# SCH_MI_L_2024-02-24.net
KiCad netlist of a schematic drawn in EasyEDA
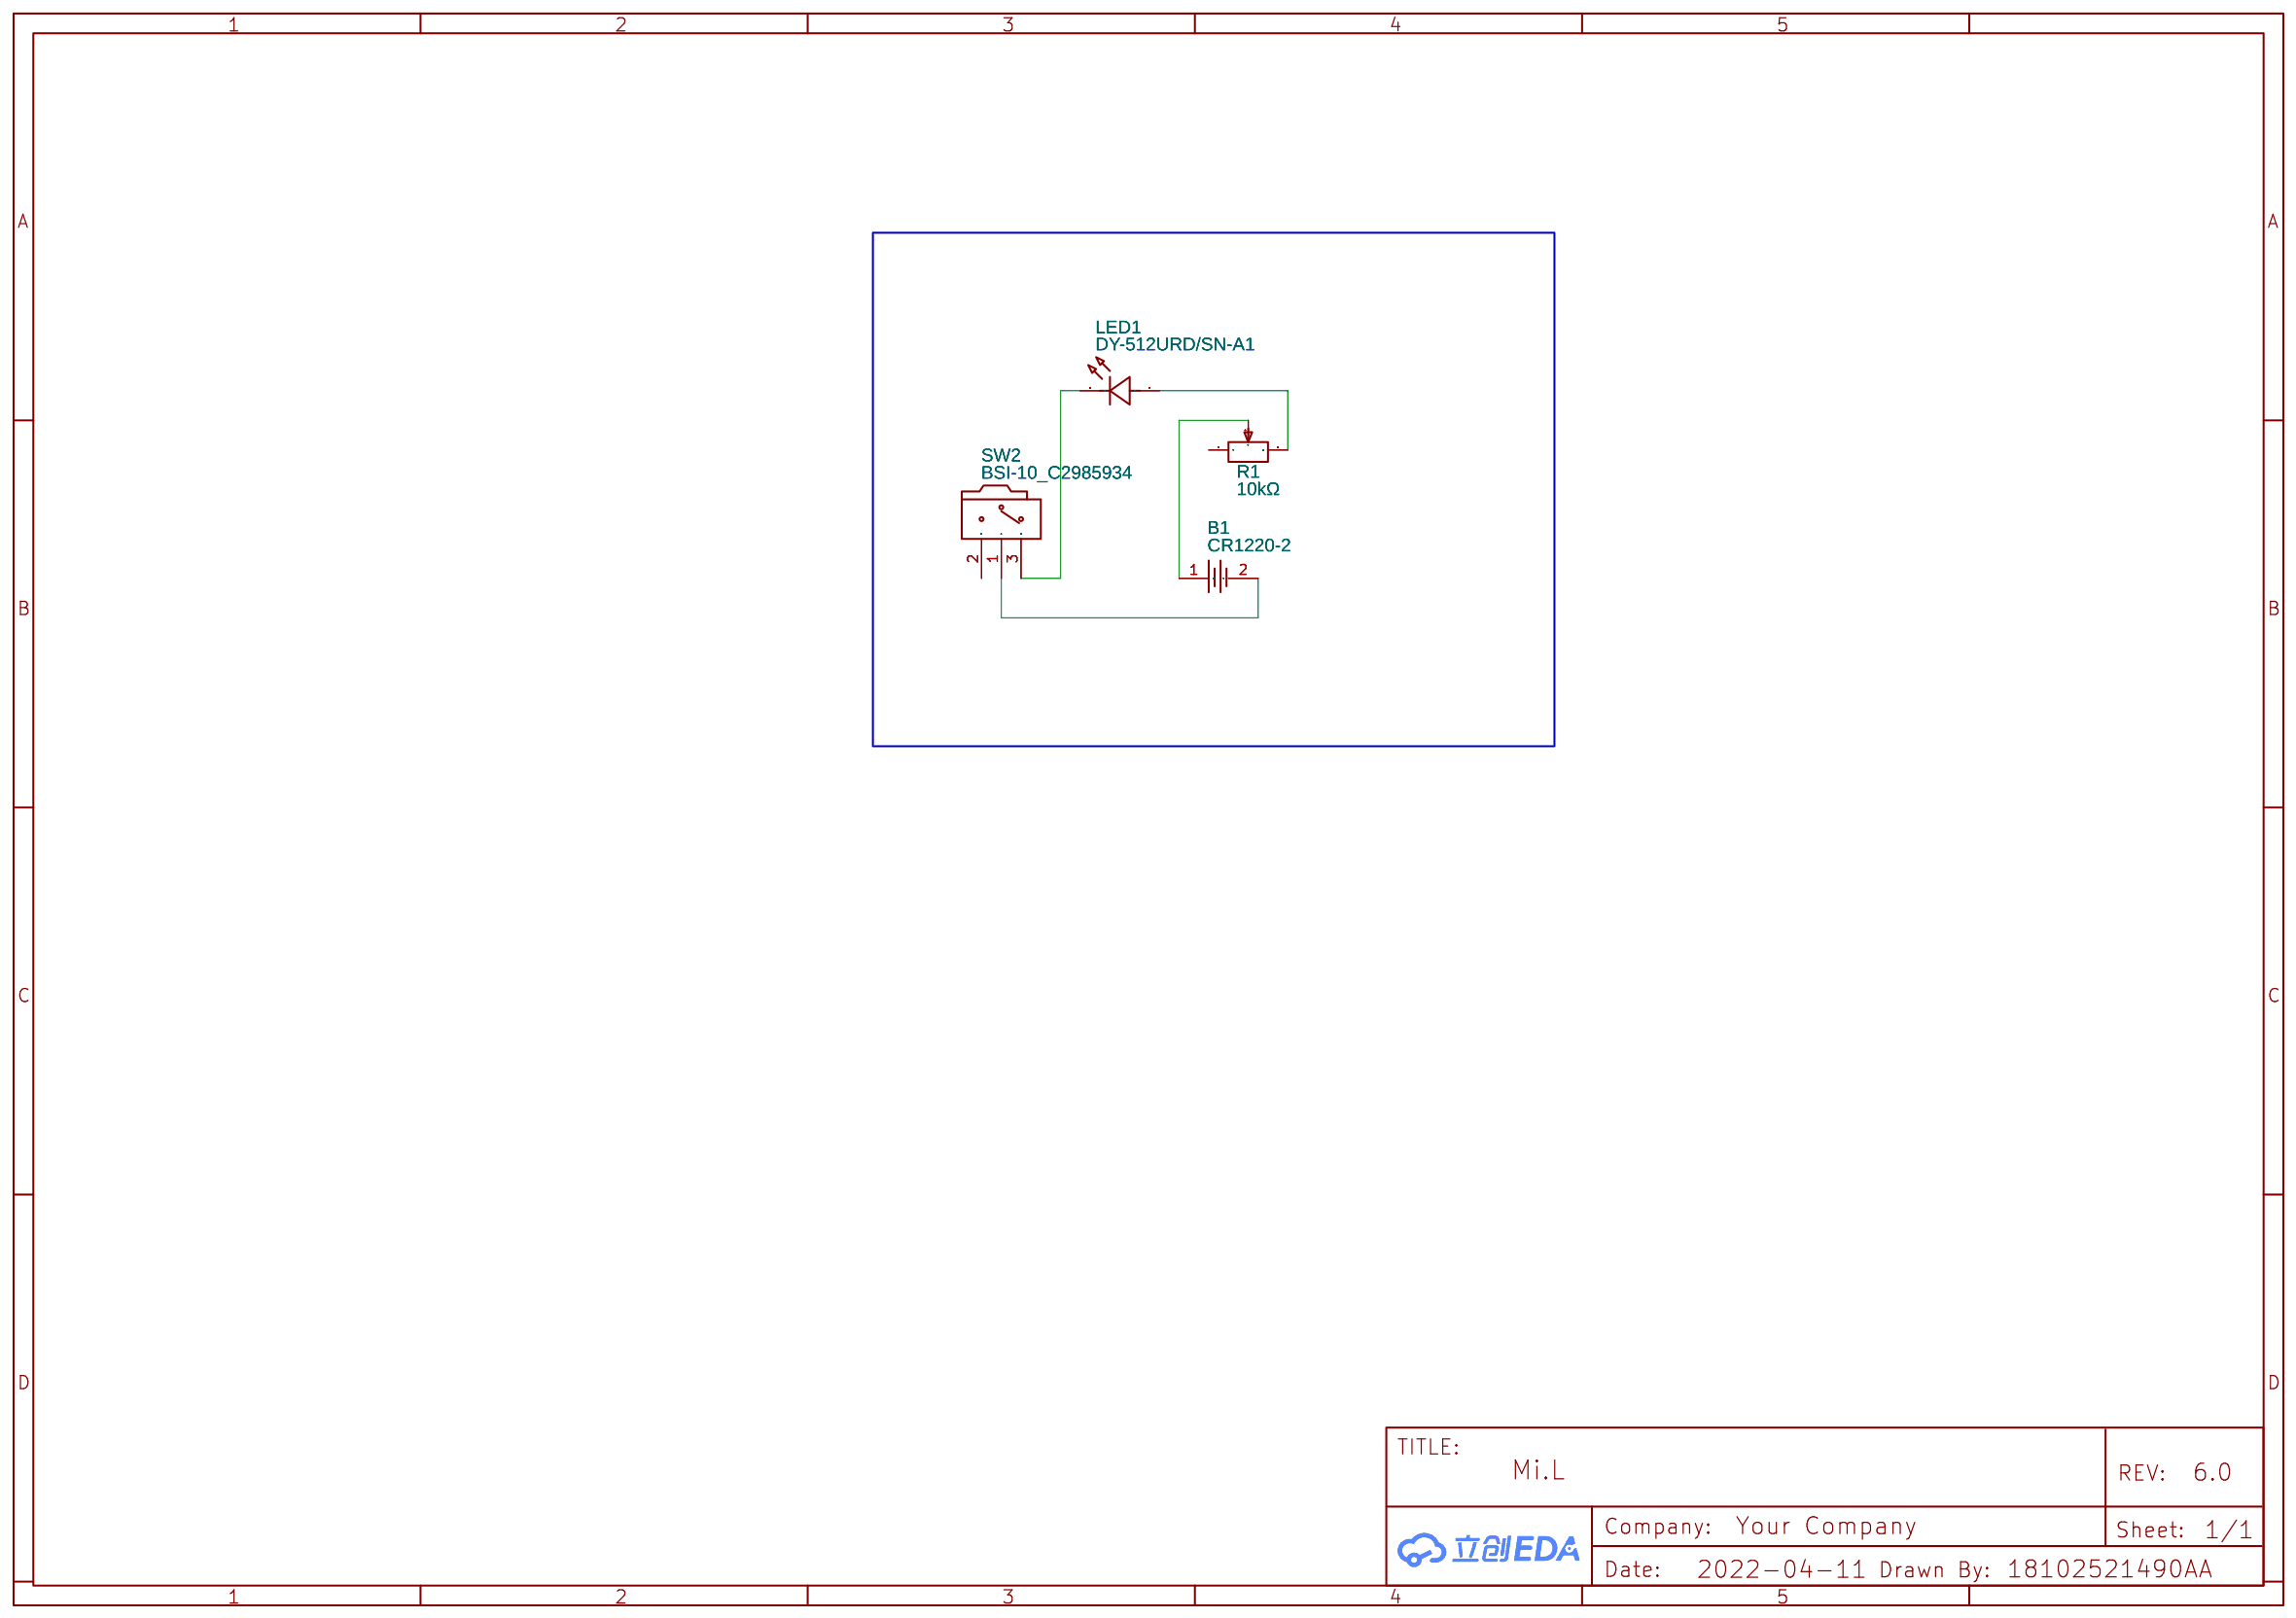
[diagram p0: schematic sheet]

(export (version "E")
  (design (tool "Eeschema 10.0.6"))
  (components
    (comp (ref "B1")
      (value "CR1220-2")
      (fields (field (name "Manufacturer") "Q&J"))
      (libsource (lib "") (part "CR1220-2"))
    )
    (comp (ref "LED1")
      (value "DY-512URD/SN-A1")
      (fields (field (name "Manufacturer") "TONYU(东裕)"))
      (libsource (lib "") (part "DY-512URD/SN-A1"))
    )
    (comp (ref "R1")
      (value "10kΩ")
      (fields (field (name "Manufacturer Part") "EVM2GSX80B14") (field (name "Manufacturer") "PANASONIC"))
      (libsource (lib "") (part "EVM2GSX80B14"))
    )
    (comp (ref "SW2")
      (value "BSI-10_C2985934")
      (fields (field (name "Manufacturer Part") "BSI-10") (field (name "Manufacturer") "SM Switch"))
      (libsource (lib "") (part "BSI-10_C2985934"))
    )
  )
  (nets
    (net (code "1") (name "Net-(B1-Pad1)") (class "Default")
      (node (ref "B1") (pin "1") (pinfunction "1_1") (pintype "input"))
      (node (ref "R1") (pin "2") (pinfunction "2_2") (pintype "input"))
    )
    (net (code "2") (name "Net-(B1-Pad2)") (class "Default")
      (node (ref "B1") (pin "2") (pinfunction "2_2") (pintype "input"))
      (node (ref "SW2") (pin "1") (pinfunction "1_1") (pintype "unspecified"))
    )
    (net (code "3") (name "Net-(LED1-A)") (class "Default")
      (node (ref "LED1") (pin "1") (pinfunction "A_1") (pintype "unspecified"))
      (node (ref "R1") (pin "3") (pinfunction "3_3") (pintype "input"))
    )
    (net (code "4") (name "Net-(LED1-K)") (class "Default")
      (node (ref "LED1") (pin "2") (pinfunction "K_2") (pintype "unspecified"))
      (node (ref "SW2") (pin "3") (pinfunction "3_3") (pintype "unspecified"))
    )
    (net (code "5") (name "unconnected-(R1-Pad1)") (class "Default")
      (node (ref "R1") (pin "1") (pinfunction "1_1") (pintype "input"))
    )
    (net (code "6") (name "unconnected-(SW2-Pad2)") (class "Default")
      (node (ref "SW2") (pin "2") (pinfunction "2_2") (pintype "unspecified"))
    )
  )
)
